# WaterDetector.net
KiCad netlist of a schematic drawn in EAGLE
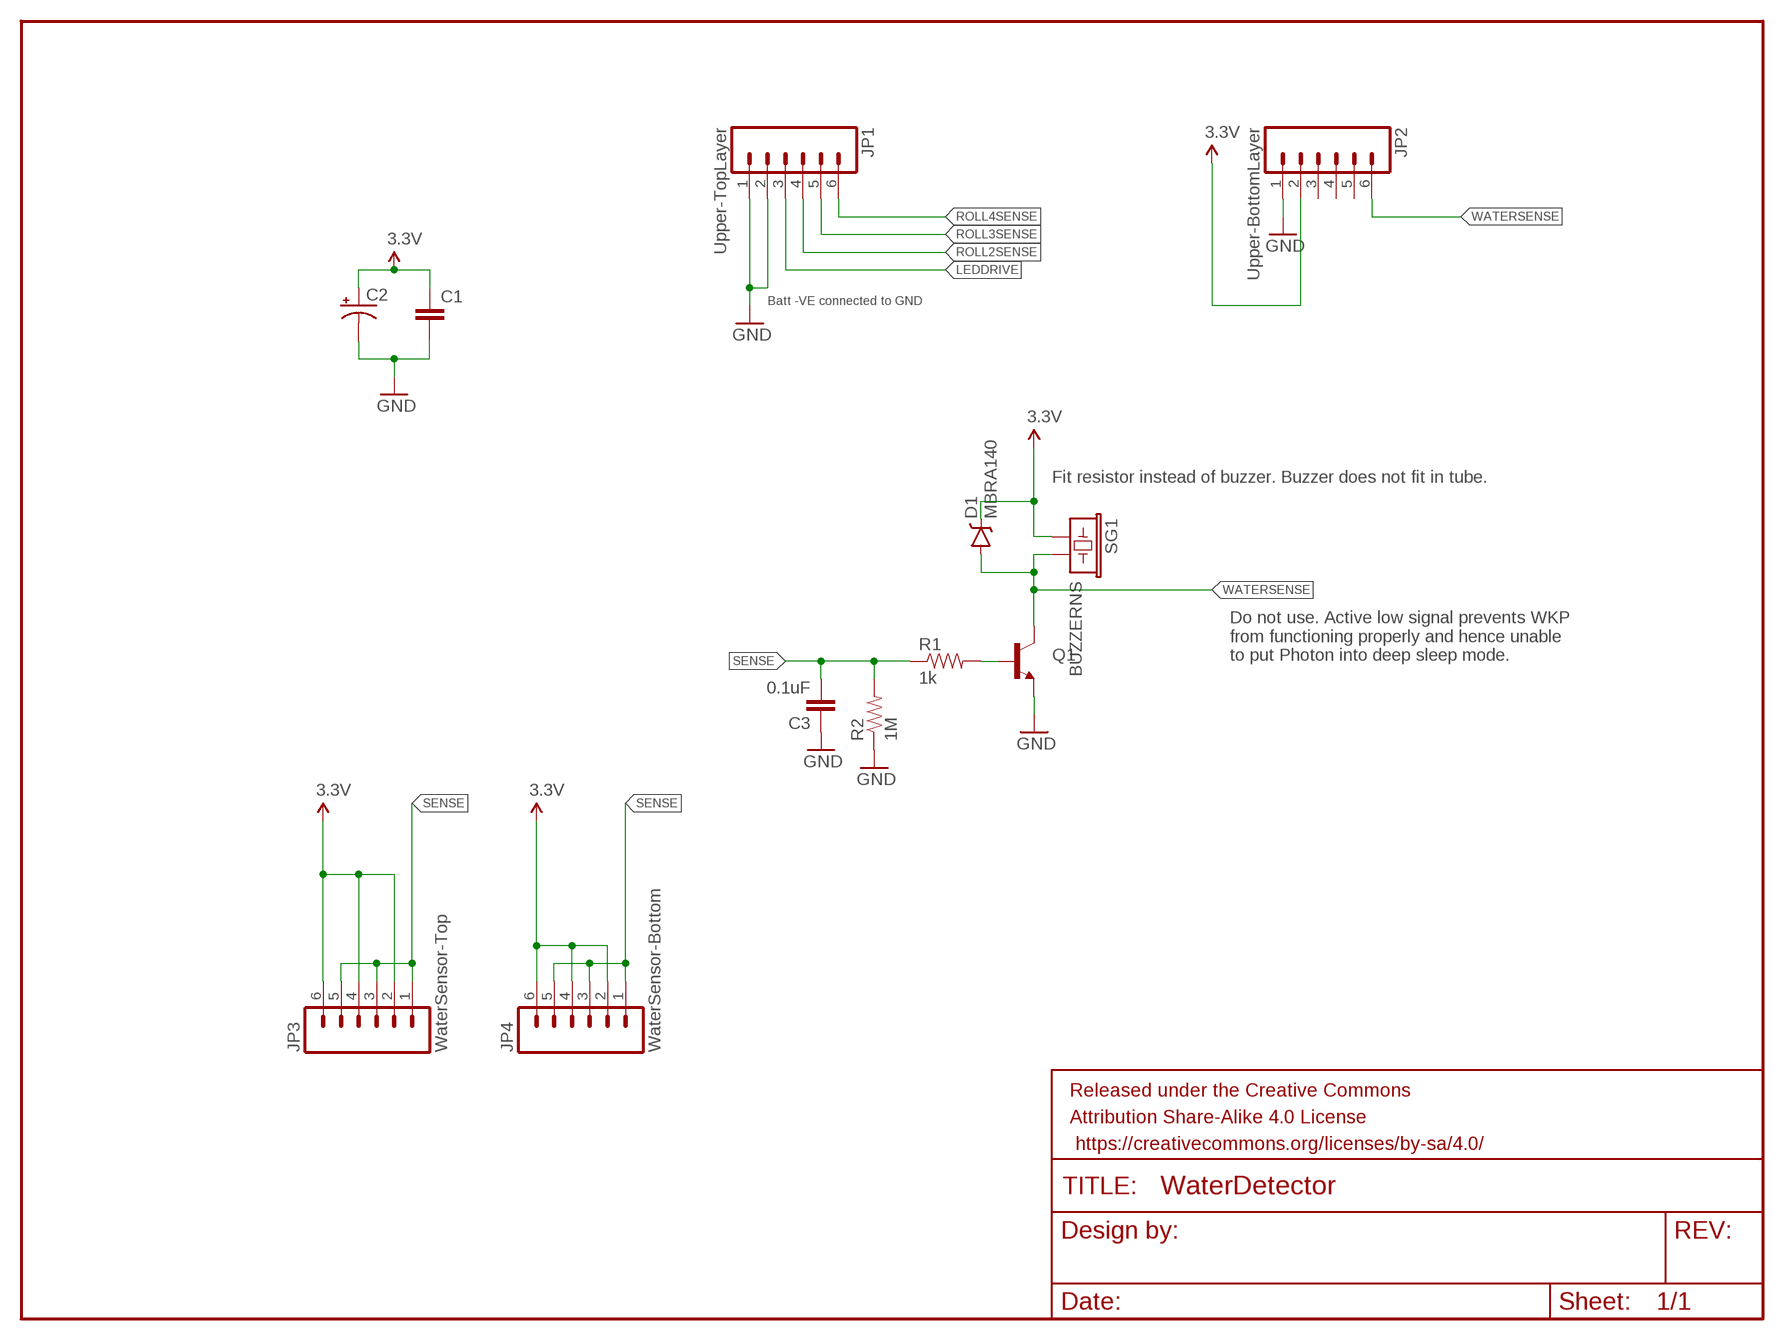
[diagram p0: schematic, sheet 1]

(export (version "E")
  (design (tool "Eeschema 10.0.6"))
  (components
    (comp (ref "C1")
      (value "CAP0805")
      (footprint "eagle-import:0805")
      (libsource (lib "eagle-import") (part "CAP0805"))
    )
    (comp (ref "C2")
      (value "CAP_POLC")
      (footprint "eagle-import:PANASONIC_C")
      (libsource (lib "eagle-import") (part "CAP_POLC"))
    )
    (comp (ref "C3")
      (value "0.1uF")
      (footprint "eagle-import:0805")
      (libsource (lib "eagle-import") (part "CAP0805"))
    )
    (comp (ref "D1")
      (value "MBRA140")
      (footprint "eagle-import:SMA-DIODE")
      (libsource (lib "eagle-import") (part "MBRA140"))
    )
    (comp (ref "FRAME1")
      (value "FRAME-LETTER")
      (footprint "eagle-import:CREATIVE_COMMONS")
      (libsource (lib "eagle-import") (part "FRAME-LETTER"))
    )
    (comp (ref "JP1")
      (value "Upper-TopLayer")
      (footprint "eagle-import:1X06-SMD_EDGE")
      (libsource (lib "eagle-import") (part "M061X06-SMD-EDGE-SOLDERLINK1X06-SMD-EDGE-SOLDERLINK"))
    )
    (comp (ref "JP2")
      (value "Upper-BottomLayer")
      (footprint "eagle-import:1X06-SMD_EDGE")
      (libsource (lib "eagle-import") (part "M061X06-SMD-EDGE-SOLDERLINK1X06-SMD-EDGE-SOLDERLINK"))
    )
    (comp (ref "JP3")
      (value "WaterSensor-Top")
      (footprint "eagle-import:1X06-SMD_EDGE")
      (libsource (lib "eagle-import") (part "M061X06-SMD-EDGE-SOLDERLINK1X06-SMD-EDGE-SOLDERLINK"))
    )
    (comp (ref "JP4")
      (value "WaterSensor-Bottom")
      (footprint "eagle-import:1X06-SMD_EDGE")
      (libsource (lib "eagle-import") (part "M061X06-SMD-EDGE-SOLDERLINK1X06-SMD-EDGE-SOLDERLINK"))
    )
    (comp (ref "Q1")
      (value "TRANSISTOR_NPNSOT23-3")
      (footprint "eagle-import:SOT23-3")
      (libsource (lib "eagle-import") (part "TRANSISTOR_NPNSOT23-3"))
    )
    (comp (ref "R1")
      (value "1k")
      (footprint "eagle-import:1206")
      (libsource (lib "eagle-import") (part "RESISTOR1206"))
    )
    (comp (ref "R2")
      (value "1M")
      (footprint "eagle-import:1206")
      (libsource (lib "eagle-import") (part "RESISTOR1206"))
    )
    (comp (ref "SG1")
      (value "BUZZERNS")
      (footprint "eagle-import:BUZZER-12MM-NS")
      (libsource (lib "eagle-import") (part "BUZZERNS"))
    )
  )
  (nets
    (net (code "1") (name "3.3V") (class "Default")
      (node (ref "C1") (pin "1") (pinfunction "1_1") (pintype "passive"))
      (node (ref "C2") (pin "+") (pinfunction "+_+") (pintype "passive"))
      (node (ref "D1") (pin "C") (pinfunction "C_C") (pintype "passive"))
      (node (ref "JP2") (pin "2") (pinfunction "2_2") (pintype "passive"))
      (node (ref "JP3") (pin "2") (pinfunction "2_2") (pintype "passive"))
      (node (ref "JP3") (pin "4") (pinfunction "4_4") (pintype "passive"))
      (node (ref "JP3") (pin "6") (pinfunction "6_6") (pintype "passive"))
      (node (ref "JP4") (pin "2") (pinfunction "2_2") (pintype "passive"))
      (node (ref "JP4") (pin "4") (pinfunction "4_4") (pintype "passive"))
      (node (ref "JP4") (pin "6") (pinfunction "6_6") (pintype "passive"))
      (node (ref "SG1") (pin "+") (pinfunction "1_+") (pintype "passive"))
    )
    (net (code "2") (name "GND") (class "Default")
      (node (ref "C1") (pin "2") (pinfunction "2_2") (pintype "passive"))
      (node (ref "C2") (pin "-") (pinfunction "-_-") (pintype "passive"))
      (node (ref "C3") (pin "1") (pinfunction "1_1") (pintype "passive"))
      (node (ref "JP1") (pin "1") (pinfunction "1_1") (pintype "passive"))
      (node (ref "JP1") (pin "2") (pinfunction "2_2") (pintype "passive"))
      (node (ref "JP2") (pin "1") (pinfunction "1_1") (pintype "passive"))
      (node (ref "Q1") (pin "2") (pinfunction "E_2") (pintype "passive"))
      (node (ref "R2") (pin "1") (pinfunction "1_1") (pintype "passive"))
    )
    (net (code "3") (name "LEDDRIVE") (class "Default")
      (node (ref "JP1") (pin "3") (pinfunction "3_3") (pintype "passive"))
    )
    (net (code "4") (name "Net-(Q1-B)") (class "Default")
      (node (ref "Q1") (pin "1") (pinfunction "B_1") (pintype "passive"))
      (node (ref "R1") (pin "2") (pinfunction "2_2") (pintype "passive"))
    )
    (net (code "5") (name "ROLL2SENSE") (class "Default")
      (node (ref "JP1") (pin "4") (pinfunction "4_4") (pintype "passive"))
    )
    (net (code "6") (name "ROLL3SENSE") (class "Default")
      (node (ref "JP1") (pin "5") (pinfunction "5_5") (pintype "passive"))
    )
    (net (code "7") (name "ROLL4SENSE") (class "Default")
      (node (ref "JP1") (pin "6") (pinfunction "6_6") (pintype "passive"))
    )
    (net (code "8") (name "SENSE") (class "Default")
      (node (ref "C3") (pin "2") (pinfunction "2_2") (pintype "passive"))
      (node (ref "JP3") (pin "1") (pinfunction "1_1") (pintype "passive"))
      (node (ref "JP3") (pin "3") (pinfunction "3_3") (pintype "passive"))
      (node (ref "JP3") (pin "5") (pinfunction "5_5") (pintype "passive"))
      (node (ref "JP4") (pin "1") (pinfunction "1_1") (pintype "passive"))
      (node (ref "JP4") (pin "3") (pinfunction "3_3") (pintype "passive"))
      (node (ref "JP4") (pin "5") (pinfunction "5_5") (pintype "passive"))
      (node (ref "R1") (pin "1") (pinfunction "1_1") (pintype "passive"))
      (node (ref "R2") (pin "2") (pinfunction "2_2") (pintype "passive"))
    )
    (net (code "9") (name "WATERSENSE") (class "Default")
      (node (ref "D1") (pin "A") (pinfunction "A_A") (pintype "passive"))
      (node (ref "JP2") (pin "6") (pinfunction "6_6") (pintype "passive"))
      (node (ref "Q1") (pin "3") (pinfunction "C_3") (pintype "passive"))
      (node (ref "SG1") (pin "-") (pinfunction "2_-") (pintype "passive"))
    )
    (net (code "10") (name "unconnected-(JP2-Pad3)") (class "Default")
      (node (ref "JP2") (pin "3") (pinfunction "3_3") (pintype "passive"))
    )
    (net (code "11") (name "unconnected-(JP2-Pad4)") (class "Default")
      (node (ref "JP2") (pin "4") (pinfunction "4_4") (pintype "passive"))
    )
    (net (code "12") (name "unconnected-(JP2-Pad5)") (class "Default")
      (node (ref "JP2") (pin "5") (pinfunction "5_5") (pintype "passive"))
    )
  )
)
